# funk.net
KiCad netlist of a schematic drawn in EAGLE
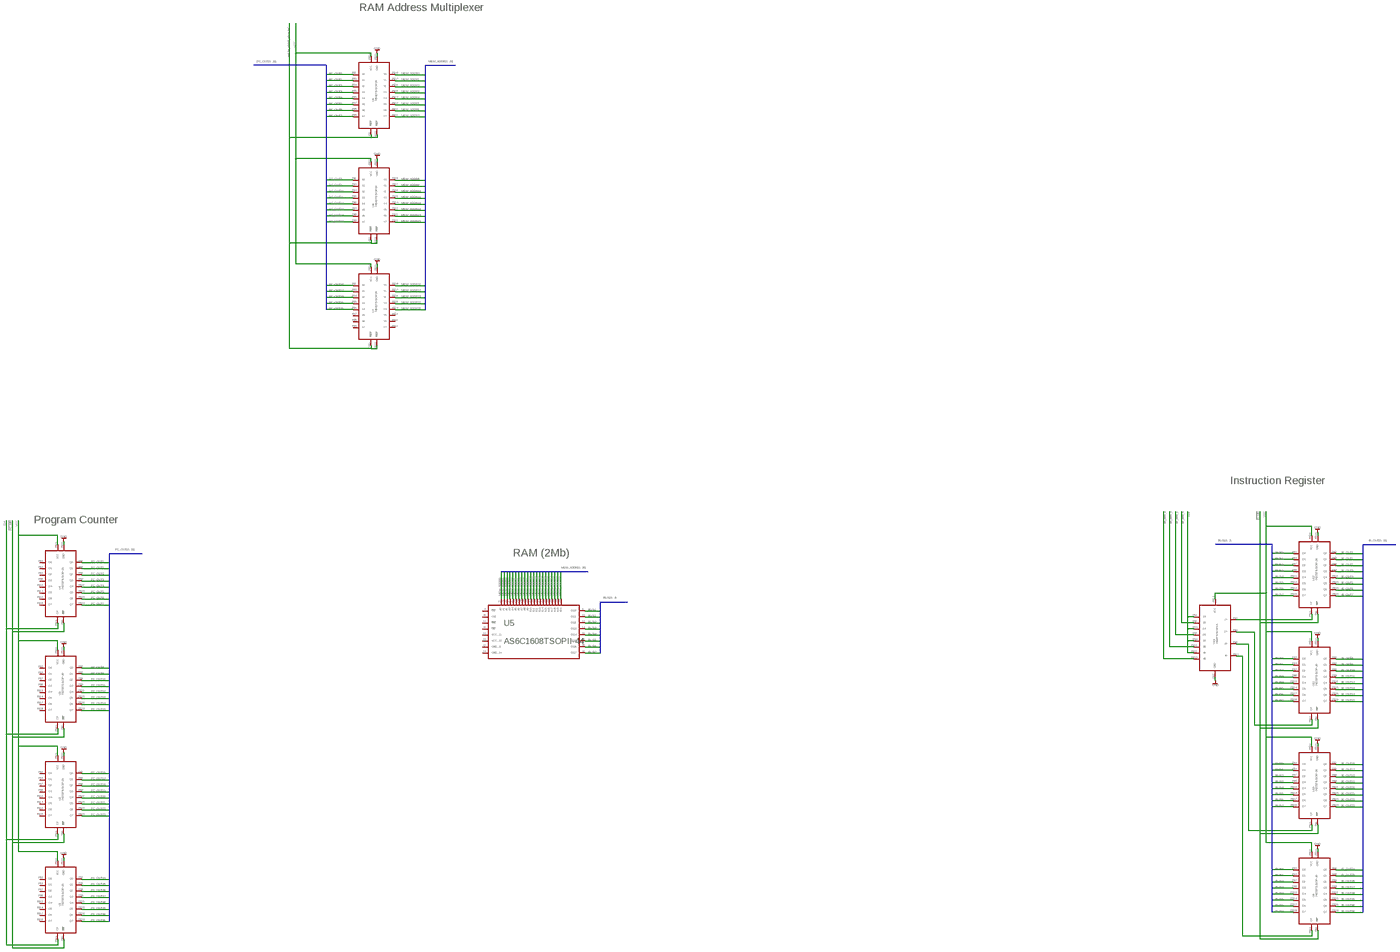
[diagram p0: schematic, sheet 1, overview]
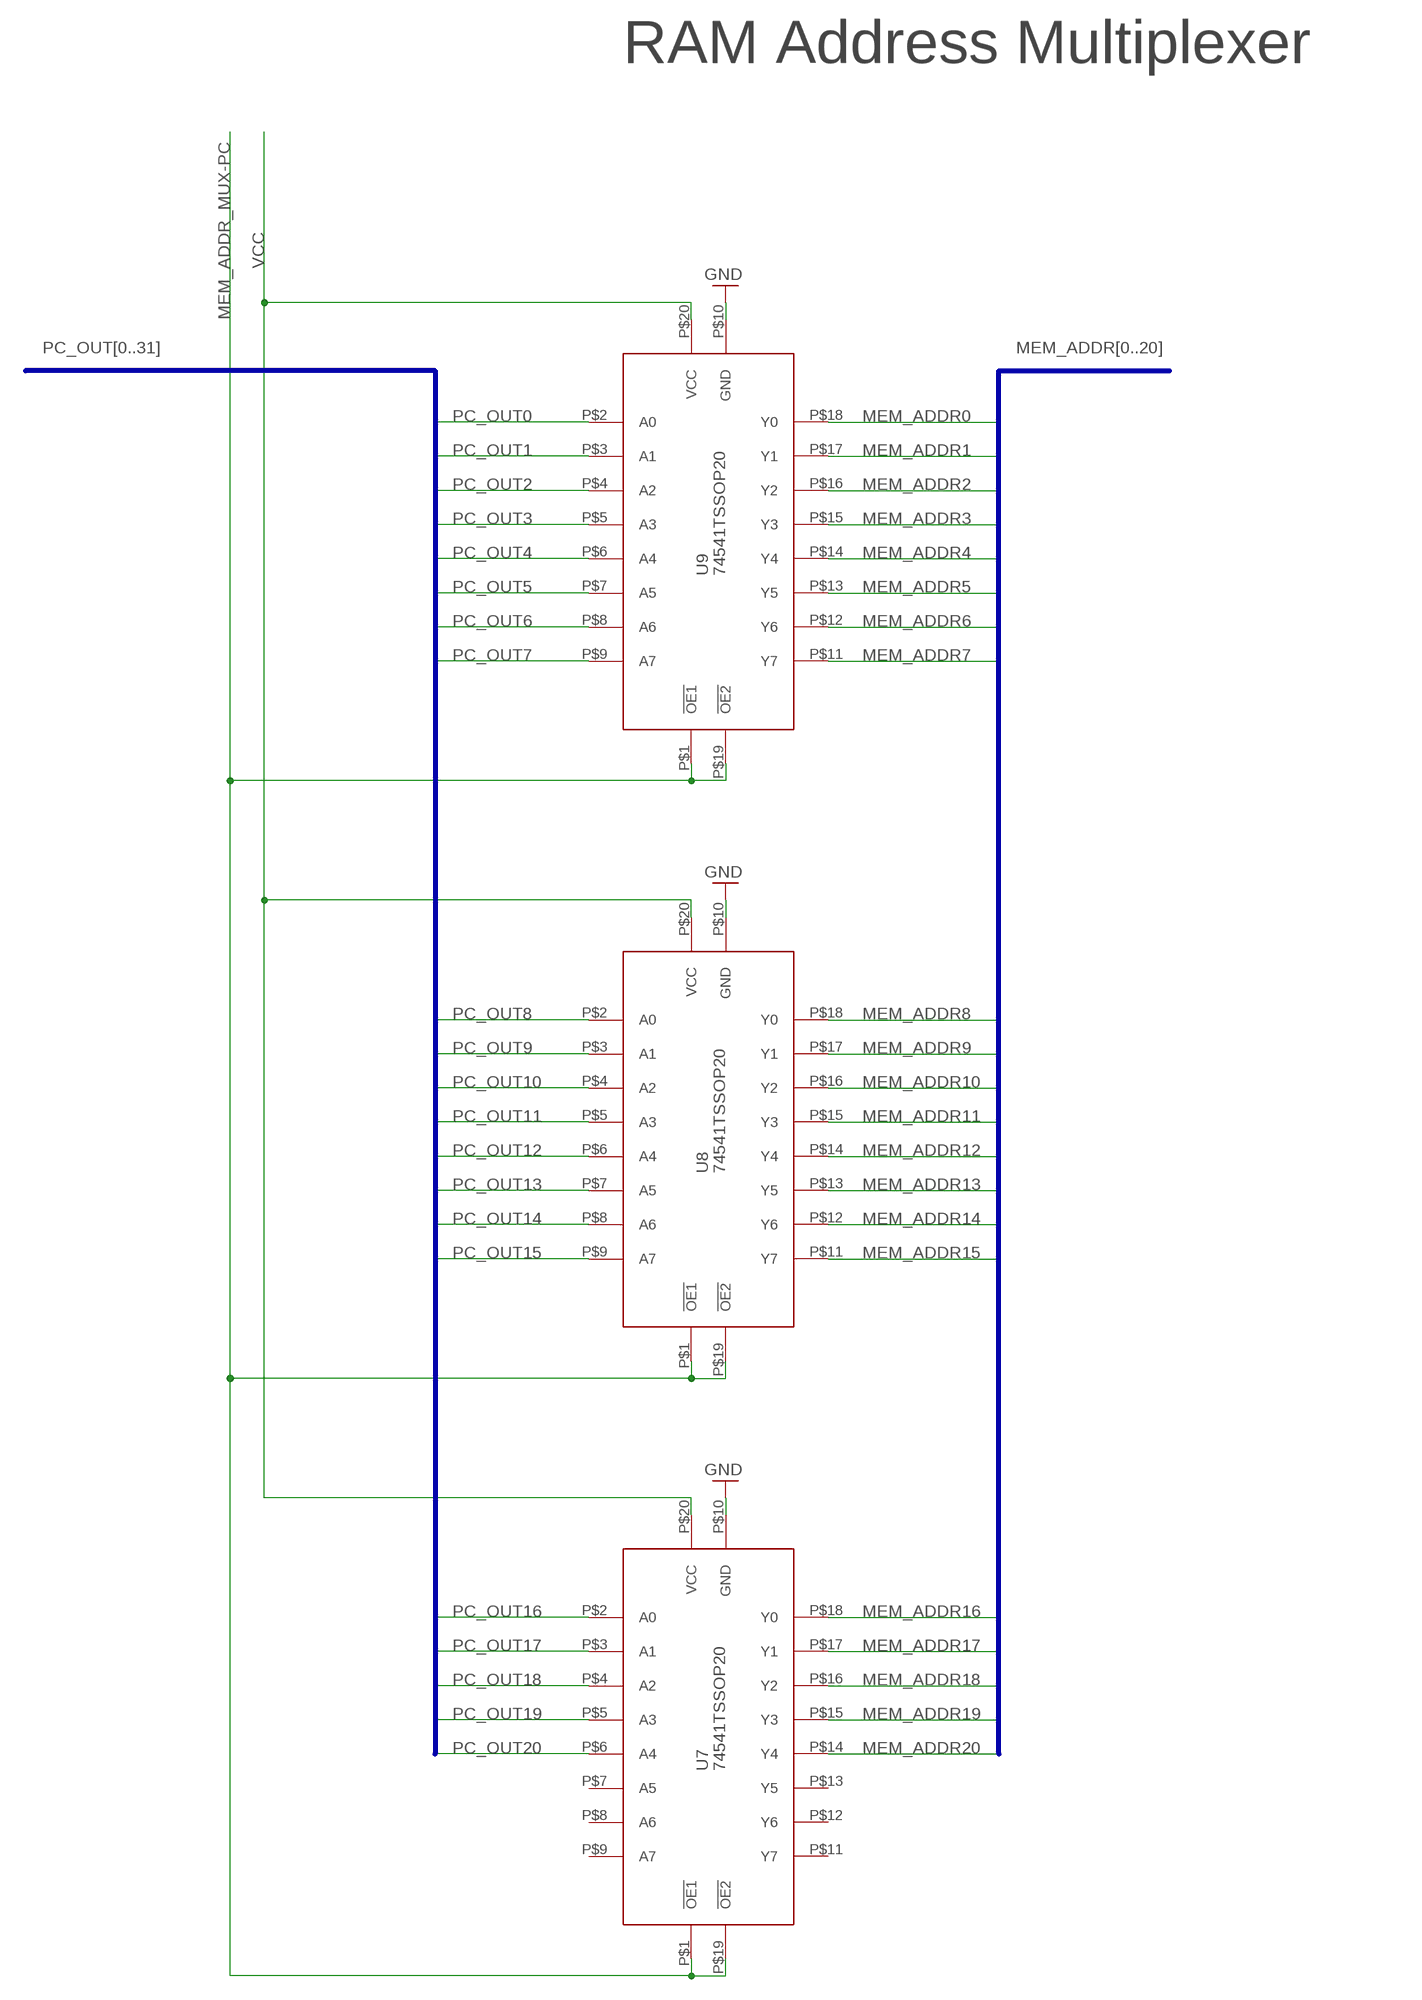
[diagram p1: schematic, sheet 1, part 1 of 4]
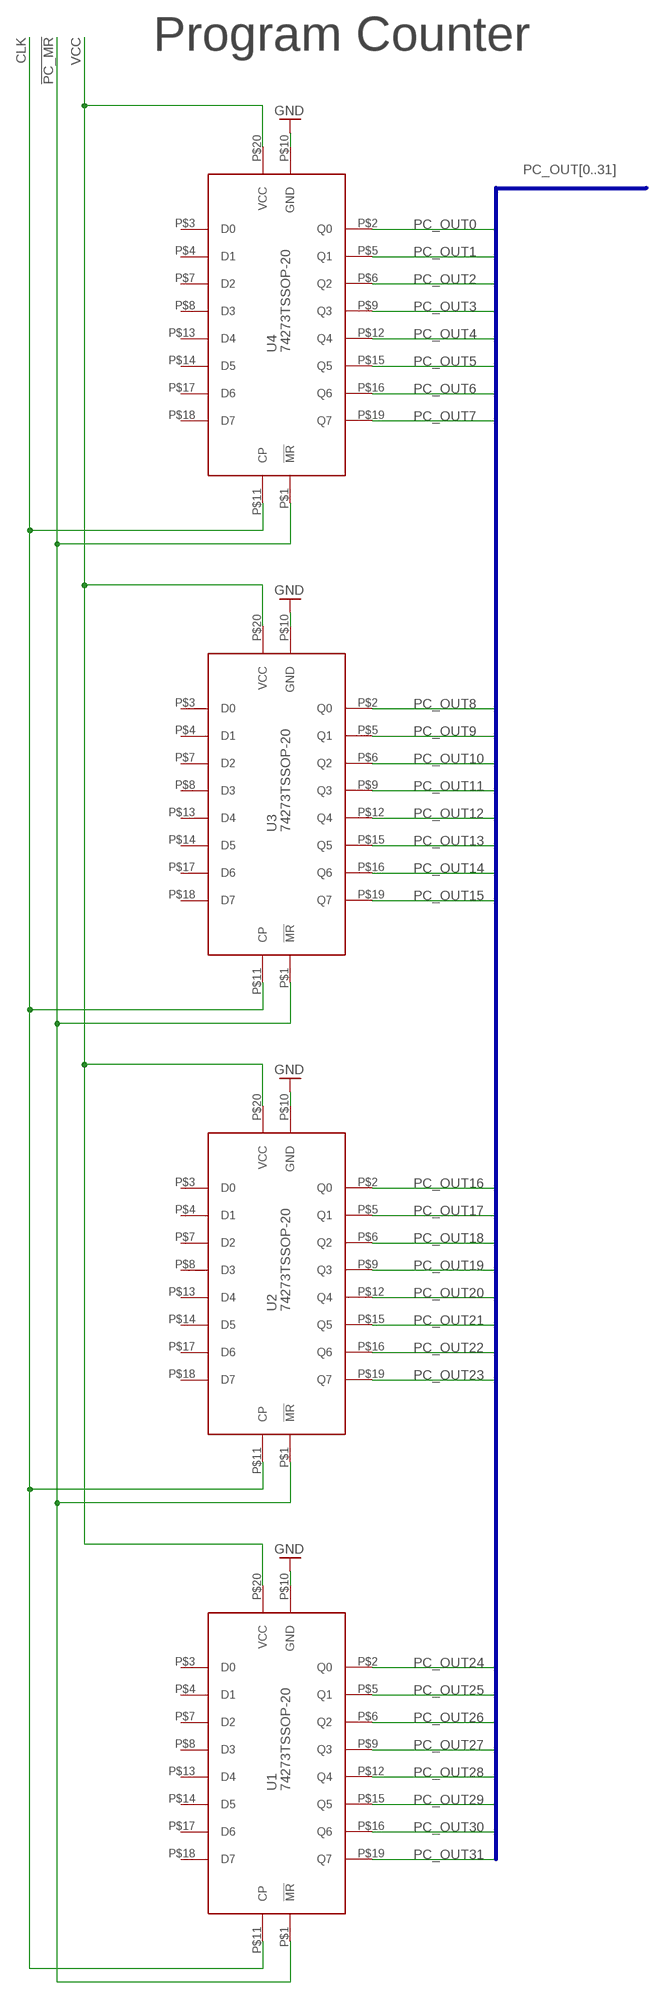
[diagram p2: schematic, sheet 1, part 2 of 4]
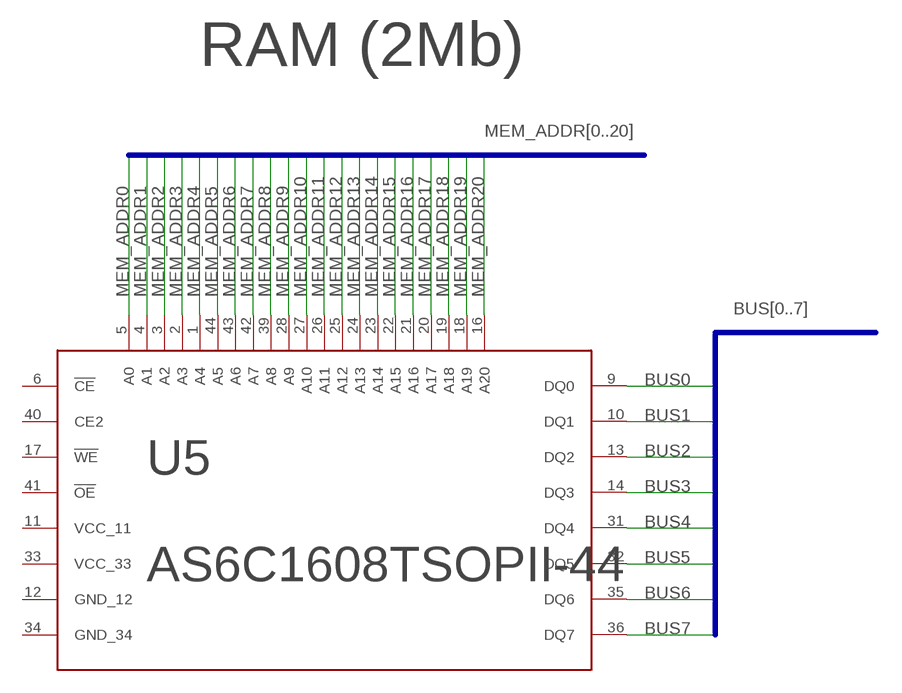
[diagram p3: schematic, sheet 1, part 3 of 4]
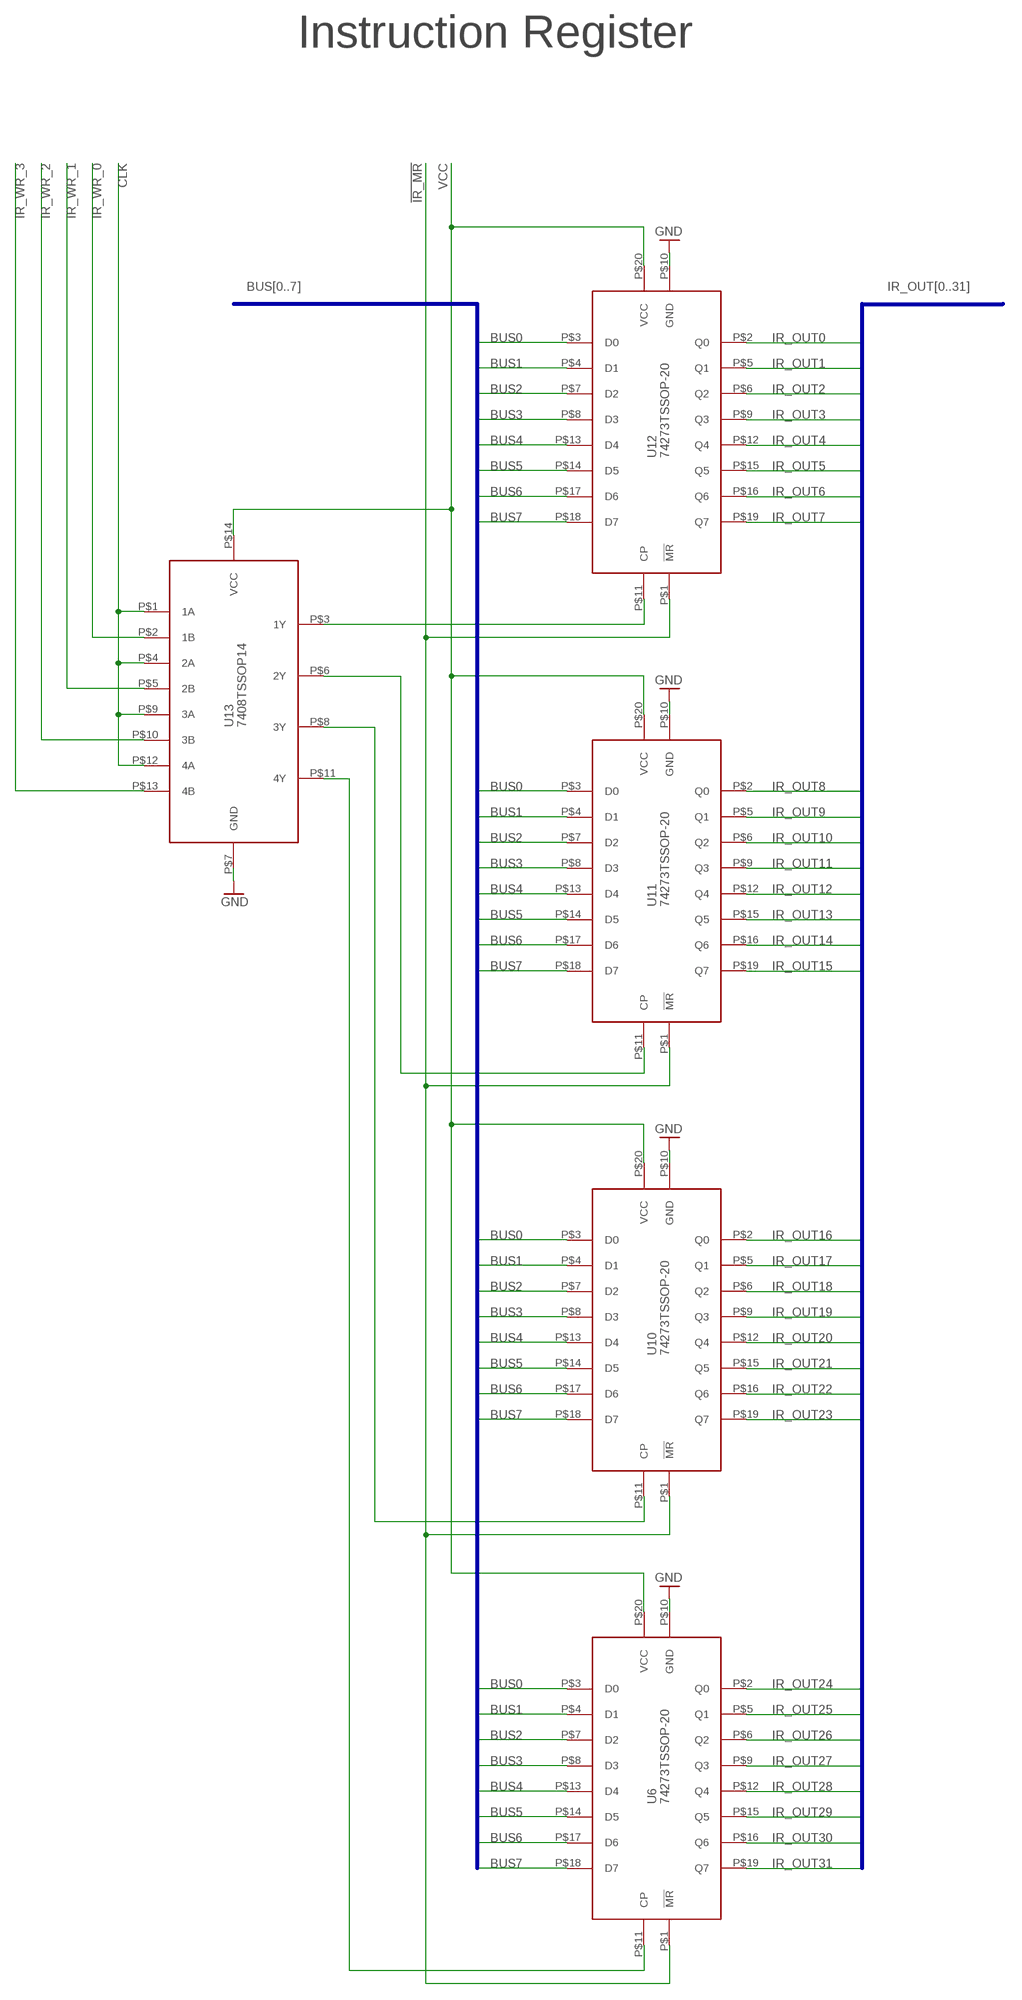
[diagram p4: schematic, sheet 1, part 4 of 4]

(export (version "E")
  (design (tool "Eeschema 10.0.6"))
  (components
    (comp (ref "U1")
      (value "74273TSSOP-20")
      (footprint "eagle-import:TSSOP-20")
      (libsource (lib "eagle-import") (part "74273TSSOP-20"))
    )
    (comp (ref "U2")
      (value "74273TSSOP-20")
      (footprint "eagle-import:TSSOP-20")
      (libsource (lib "eagle-import") (part "74273TSSOP-20"))
    )
    (comp (ref "U3")
      (value "74273TSSOP-20")
      (footprint "eagle-import:TSSOP-20")
      (libsource (lib "eagle-import") (part "74273TSSOP-20"))
    )
    (comp (ref "U4")
      (value "74273TSSOP-20")
      (footprint "eagle-import:TSSOP-20")
      (libsource (lib "eagle-import") (part "74273TSSOP-20"))
    )
    (comp (ref "U5")
      (value "AS6C1608TSOPII-44")
      (footprint "eagle-import:TSOPII-44")
      (libsource (lib "eagle-import") (part "AS6C1608TSOPII-44"))
    )
    (comp (ref "U6")
      (value "74273TSSOP-20")
      (footprint "eagle-import:TSSOP-20")
      (libsource (lib "eagle-import") (part "74273TSSOP-20"))
    )
    (comp (ref "U7")
      (value "74541TSSOP20")
      (footprint "eagle-import:TSSOP-20")
      (libsource (lib "eagle-import") (part "74541TSSOP20"))
    )
    (comp (ref "U8")
      (value "74541TSSOP20")
      (footprint "eagle-import:TSSOP-20")
      (libsource (lib "eagle-import") (part "74541TSSOP20"))
    )
    (comp (ref "U9")
      (value "74541TSSOP20")
      (footprint "eagle-import:TSSOP-20")
      (libsource (lib "eagle-import") (part "74541TSSOP20"))
    )
    (comp (ref "U10")
      (value "74273TSSOP-20")
      (footprint "eagle-import:TSSOP-20")
      (libsource (lib "eagle-import") (part "74273TSSOP-20"))
    )
    (comp (ref "U11")
      (value "74273TSSOP-20")
      (footprint "eagle-import:TSSOP-20")
      (libsource (lib "eagle-import") (part "74273TSSOP-20"))
    )
    (comp (ref "U12")
      (value "74273TSSOP-20")
      (footprint "eagle-import:TSSOP-20")
      (libsource (lib "eagle-import") (part "74273TSSOP-20"))
    )
    (comp (ref "U13")
      (value "7408TSSOP14")
      (footprint "eagle-import:TSSOP-14")
      (libsource (lib "eagle-import") (part "7408TSSOP14"))
    )
  )
  (nets
    (net (code "1") (name "/BUS0") (class "Default")
      (node (ref "U10") (pin "P$3") (pinfunction "D0_P$3") (pintype "bidirectional"))
      (node (ref "U11") (pin "P$3") (pinfunction "D0_P$3") (pintype "bidirectional"))
      (node (ref "U12") (pin "P$3") (pinfunction "D0_P$3") (pintype "bidirectional"))
      (node (ref "U5") (pin "9") (pinfunction "DQ0_9") (pintype "bidirectional"))
      (node (ref "U6") (pin "P$3") (pinfunction "D0_P$3") (pintype "bidirectional"))
    )
    (net (code "2") (name "/BUS1") (class "Default")
      (node (ref "U10") (pin "P$4") (pinfunction "D1_P$4") (pintype "bidirectional"))
      (node (ref "U11") (pin "P$4") (pinfunction "D1_P$4") (pintype "bidirectional"))
      (node (ref "U12") (pin "P$4") (pinfunction "D1_P$4") (pintype "bidirectional"))
      (node (ref "U5") (pin "10") (pinfunction "DQ1_10") (pintype "bidirectional"))
      (node (ref "U6") (pin "P$4") (pinfunction "D1_P$4") (pintype "bidirectional"))
    )
    (net (code "3") (name "/BUS2") (class "Default")
      (node (ref "U10") (pin "P$7") (pinfunction "D2_P$7") (pintype "bidirectional"))
      (node (ref "U11") (pin "P$7") (pinfunction "D2_P$7") (pintype "bidirectional"))
      (node (ref "U12") (pin "P$7") (pinfunction "D2_P$7") (pintype "bidirectional"))
      (node (ref "U5") (pin "13") (pinfunction "DQ2_13") (pintype "bidirectional"))
      (node (ref "U6") (pin "P$7") (pinfunction "D2_P$7") (pintype "bidirectional"))
    )
    (net (code "4") (name "/BUS3") (class "Default")
      (node (ref "U10") (pin "P$8") (pinfunction "D3_P$8") (pintype "bidirectional"))
      (node (ref "U11") (pin "P$8") (pinfunction "D3_P$8") (pintype "bidirectional"))
      (node (ref "U12") (pin "P$8") (pinfunction "D3_P$8") (pintype "bidirectional"))
      (node (ref "U5") (pin "14") (pinfunction "DQ3_14") (pintype "bidirectional"))
      (node (ref "U6") (pin "P$8") (pinfunction "D3_P$8") (pintype "bidirectional"))
    )
    (net (code "5") (name "/BUS4") (class "Default")
      (node (ref "U10") (pin "P$13") (pinfunction "D4_P$13") (pintype "bidirectional"))
      (node (ref "U11") (pin "P$13") (pinfunction "D4_P$13") (pintype "bidirectional"))
      (node (ref "U12") (pin "P$13") (pinfunction "D4_P$13") (pintype "bidirectional"))
      (node (ref "U5") (pin "31") (pinfunction "DQ4_31") (pintype "bidirectional"))
      (node (ref "U6") (pin "P$13") (pinfunction "D4_P$13") (pintype "bidirectional"))
    )
    (net (code "6") (name "/BUS5") (class "Default")
      (node (ref "U10") (pin "P$14") (pinfunction "D5_P$14") (pintype "bidirectional"))
      (node (ref "U11") (pin "P$14") (pinfunction "D5_P$14") (pintype "bidirectional"))
      (node (ref "U12") (pin "P$14") (pinfunction "D5_P$14") (pintype "bidirectional"))
      (node (ref "U5") (pin "32") (pinfunction "DQ5_32") (pintype "bidirectional"))
      (node (ref "U6") (pin "P$14") (pinfunction "D5_P$14") (pintype "bidirectional"))
    )
    (net (code "7") (name "/BUS6") (class "Default")
      (node (ref "U10") (pin "P$17") (pinfunction "D6_P$17") (pintype "bidirectional"))
      (node (ref "U11") (pin "P$17") (pinfunction "D6_P$17") (pintype "bidirectional"))
      (node (ref "U12") (pin "P$17") (pinfunction "D6_P$17") (pintype "bidirectional"))
      (node (ref "U5") (pin "35") (pinfunction "DQ6_35") (pintype "bidirectional"))
      (node (ref "U6") (pin "P$17") (pinfunction "D6_P$17") (pintype "bidirectional"))
    )
    (net (code "8") (name "/BUS7") (class "Default")
      (node (ref "U10") (pin "P$18") (pinfunction "D7_P$18") (pintype "bidirectional"))
      (node (ref "U11") (pin "P$18") (pinfunction "D7_P$18") (pintype "bidirectional"))
      (node (ref "U12") (pin "P$18") (pinfunction "D7_P$18") (pintype "bidirectional"))
      (node (ref "U5") (pin "36") (pinfunction "DQ7_36") (pintype "bidirectional"))
      (node (ref "U6") (pin "P$18") (pinfunction "D7_P$18") (pintype "bidirectional"))
    )
    (net (code "10") (name "/CLK") (class "Default")
      (node (ref "U1") (pin "P$11") (pinfunction "CP_P$11") (pintype "bidirectional"))
      (node (ref "U10") (pin "P$11") (pinfunction "CP_P$11") (pintype "bidirectional"))
      (node (ref "U13") (pin "P$1") (pinfunction "1A_P$1") (pintype "bidirectional"))
      (node (ref "U13") (pin "P$12") (pinfunction "4A_P$12") (pintype "bidirectional"))
      (node (ref "U13") (pin "P$4") (pinfunction "2A_P$4") (pintype "bidirectional"))
      (node (ref "U13") (pin "P$8") (pinfunction "3Y_P$8") (pintype "bidirectional"))
      (node (ref "U13") (pin "P$9") (pinfunction "3A_P$9") (pintype "bidirectional"))
      (node (ref "U2") (pin "P$11") (pinfunction "CP_P$11") (pintype "bidirectional"))
      (node (ref "U3") (pin "P$11") (pinfunction "CP_P$11") (pintype "bidirectional"))
      (node (ref "U4") (pin "P$11") (pinfunction "CP_P$11") (pintype "bidirectional"))
    )
    (net (code "11") (name "/IR_OUT0") (class "Default")
      (node (ref "U12") (pin "P$2") (pinfunction "Q0_P$2") (pintype "bidirectional"))
    )
    (net (code "12") (name "/IR_OUT1") (class "Default")
      (node (ref "U12") (pin "P$5") (pinfunction "Q1_P$5") (pintype "bidirectional"))
    )
    (net (code "13") (name "/IR_OUT2") (class "Default")
      (node (ref "U12") (pin "P$6") (pinfunction "Q2_P$6") (pintype "bidirectional"))
    )
    (net (code "14") (name "/IR_OUT3") (class "Default")
      (node (ref "U12") (pin "P$9") (pinfunction "Q3_P$9") (pintype "bidirectional"))
    )
    (net (code "15") (name "/IR_OUT4") (class "Default")
      (node (ref "U12") (pin "P$12") (pinfunction "Q4_P$12") (pintype "bidirectional"))
    )
    (net (code "16") (name "/IR_OUT5") (class "Default")
      (node (ref "U12") (pin "P$15") (pinfunction "Q5_P$15") (pintype "bidirectional"))
    )
    (net (code "17") (name "/IR_OUT6") (class "Default")
      (node (ref "U12") (pin "P$16") (pinfunction "Q6_P$16") (pintype "bidirectional"))
    )
    (net (code "18") (name "/IR_OUT7") (class "Default")
      (node (ref "U12") (pin "P$19") (pinfunction "Q7_P$19") (pintype "bidirectional"))
    )
    (net (code "19") (name "/IR_OUT8") (class "Default")
      (node (ref "U11") (pin "P$2") (pinfunction "Q0_P$2") (pintype "bidirectional"))
    )
    (net (code "20") (name "/IR_OUT9") (class "Default")
      (node (ref "U11") (pin "P$5") (pinfunction "Q1_P$5") (pintype "bidirectional"))
    )
    (net (code "21") (name "/IR_OUT10") (class "Default")
      (node (ref "U11") (pin "P$6") (pinfunction "Q2_P$6") (pintype "bidirectional"))
    )
    (net (code "22") (name "/IR_OUT11") (class "Default")
      (node (ref "U11") (pin "P$9") (pinfunction "Q3_P$9") (pintype "bidirectional"))
    )
    (net (code "23") (name "/IR_OUT12") (class "Default")
      (node (ref "U11") (pin "P$12") (pinfunction "Q4_P$12") (pintype "bidirectional"))
    )
    (net (code "24") (name "/IR_OUT13") (class "Default")
      (node (ref "U11") (pin "P$15") (pinfunction "Q5_P$15") (pintype "bidirectional"))
    )
    (net (code "25") (name "/IR_OUT14") (class "Default")
      (node (ref "U11") (pin "P$16") (pinfunction "Q6_P$16") (pintype "bidirectional"))
    )
    (net (code "26") (name "/IR_OUT15") (class "Default")
      (node (ref "U11") (pin "P$19") (pinfunction "Q7_P$19") (pintype "bidirectional"))
    )
    (net (code "27") (name "/IR_OUT16") (class "Default")
      (node (ref "U10") (pin "P$2") (pinfunction "Q0_P$2") (pintype "bidirectional"))
    )
    (net (code "28") (name "/IR_OUT17") (class "Default")
      (node (ref "U10") (pin "P$5") (pinfunction "Q1_P$5") (pintype "bidirectional"))
    )
    (net (code "29") (name "/IR_OUT18") (class "Default")
      (node (ref "U10") (pin "P$6") (pinfunction "Q2_P$6") (pintype "bidirectional"))
    )
    (net (code "30") (name "/IR_OUT19") (class "Default")
      (node (ref "U10") (pin "P$9") (pinfunction "Q3_P$9") (pintype "bidirectional"))
    )
    (net (code "31") (name "/IR_OUT20") (class "Default")
      (node (ref "U10") (pin "P$12") (pinfunction "Q4_P$12") (pintype "bidirectional"))
    )
    (net (code "32") (name "/IR_OUT21") (class "Default")
      (node (ref "U10") (pin "P$15") (pinfunction "Q5_P$15") (pintype "bidirectional"))
    )
    (net (code "33") (name "/IR_OUT22") (class "Default")
      (node (ref "U10") (pin "P$16") (pinfunction "Q6_P$16") (pintype "bidirectional"))
    )
    (net (code "34") (name "/IR_OUT23") (class "Default")
      (node (ref "U10") (pin "P$19") (pinfunction "Q7_P$19") (pintype "bidirectional"))
    )
    (net (code "35") (name "/IR_OUT24") (class "Default")
      (node (ref "U6") (pin "P$2") (pinfunction "Q0_P$2") (pintype "bidirectional"))
    )
    (net (code "36") (name "/IR_OUT25") (class "Default")
      (node (ref "U6") (pin "P$5") (pinfunction "Q1_P$5") (pintype "bidirectional"))
    )
    (net (code "37") (name "/IR_OUT26") (class "Default")
      (node (ref "U6") (pin "P$6") (pinfunction "Q2_P$6") (pintype "bidirectional"))
    )
    (net (code "38") (name "/IR_OUT27") (class "Default")
      (node (ref "U6") (pin "P$9") (pinfunction "Q3_P$9") (pintype "bidirectional"))
    )
    (net (code "39") (name "/IR_OUT28") (class "Default")
      (node (ref "U6") (pin "P$12") (pinfunction "Q4_P$12") (pintype "bidirectional"))
    )
    (net (code "40") (name "/IR_OUT29") (class "Default")
      (node (ref "U6") (pin "P$15") (pinfunction "Q5_P$15") (pintype "bidirectional"))
    )
    (net (code "41") (name "/IR_OUT30") (class "Default")
      (node (ref "U6") (pin "P$16") (pinfunction "Q6_P$16") (pintype "bidirectional"))
    )
    (net (code "42") (name "/IR_OUT31") (class "Default")
      (node (ref "U6") (pin "P$19") (pinfunction "Q7_P$19") (pintype "bidirectional"))
    )
    (net (code "44") (name "/IR_WR_0") (class "Default")
      (node (ref "U13") (pin "P$2") (pinfunction "1B_P$2") (pintype "bidirectional"))
    )
    (net (code "45") (name "/IR_WR_1") (class "Default")
      (node (ref "U13") (pin "P$5") (pinfunction "2B_P$5") (pintype "bidirectional"))
    )
    (net (code "46") (name "/IR_WR_2") (class "Default")
      (node (ref "U13") (pin "P$10") (pinfunction "3B_P$10") (pintype "bidirectional"))
    )
    (net (code "47") (name "/IR_WR_3") (class "Default")
      (node (ref "U13") (pin "P$13") (pinfunction "4B_P$13") (pintype "bidirectional"))
    )
    (net (code "48") (name "/MEM_ADDR0") (class "Default")
      (node (ref "U5") (pin "5") (pinfunction "A0_5") (pintype "bidirectional"))
      (node (ref "U9") (pin "P$18") (pinfunction "Y0_P$18") (pintype "bidirectional"))
    )
    (net (code "49") (name "/MEM_ADDR1") (class "Default")
      (node (ref "U5") (pin "4") (pinfunction "A1_4") (pintype "bidirectional"))
      (node (ref "U9") (pin "P$17") (pinfunction "Y1_P$17") (pintype "bidirectional"))
    )
    (net (code "50") (name "/MEM_ADDR2") (class "Default")
      (node (ref "U5") (pin "3") (pinfunction "A2_3") (pintype "bidirectional"))
      (node (ref "U9") (pin "P$16") (pinfunction "Y2_P$16") (pintype "bidirectional"))
    )
    (net (code "51") (name "/MEM_ADDR3") (class "Default")
      (node (ref "U5") (pin "2") (pinfunction "A3_2") (pintype "bidirectional"))
      (node (ref "U9") (pin "P$15") (pinfunction "Y3_P$15") (pintype "bidirectional"))
    )
    (net (code "52") (name "/MEM_ADDR4") (class "Default")
      (node (ref "U5") (pin "1") (pinfunction "A4_1") (pintype "bidirectional"))
      (node (ref "U9") (pin "P$14") (pinfunction "Y4_P$14") (pintype "bidirectional"))
    )
    (net (code "53") (name "/MEM_ADDR5") (class "Default")
      (node (ref "U5") (pin "44") (pinfunction "A5_44") (pintype "bidirectional"))
      (node (ref "U9") (pin "P$13") (pinfunction "Y5_P$13") (pintype "bidirectional"))
    )
    (net (code "54") (name "/MEM_ADDR6") (class "Default")
      (node (ref "U5") (pin "43") (pinfunction "A6_43") (pintype "bidirectional"))
      (node (ref "U9") (pin "P$12") (pinfunction "Y6_P$12") (pintype "bidirectional"))
    )
    (net (code "55") (name "/MEM_ADDR7") (class "Default")
      (node (ref "U5") (pin "42") (pinfunction "A7_42") (pintype "bidirectional"))
      (node (ref "U9") (pin "P$11") (pinfunction "Y7_P$11") (pintype "bidirectional"))
    )
    (net (code "56") (name "/MEM_ADDR8") (class "Default")
      (node (ref "U5") (pin "39") (pinfunction "A8_39") (pintype "bidirectional"))
      (node (ref "U8") (pin "P$18") (pinfunction "Y0_P$18") (pintype "bidirectional"))
    )
    (net (code "57") (name "/MEM_ADDR9") (class "Default")
      (node (ref "U5") (pin "28") (pinfunction "A9_28") (pintype "bidirectional"))
      (node (ref "U8") (pin "P$17") (pinfunction "Y1_P$17") (pintype "bidirectional"))
    )
    (net (code "58") (name "/MEM_ADDR10") (class "Default")
      (node (ref "U5") (pin "27") (pinfunction "A10_27") (pintype "bidirectional"))
      (node (ref "U8") (pin "P$16") (pinfunction "Y2_P$16") (pintype "bidirectional"))
    )
    (net (code "59") (name "/MEM_ADDR11") (class "Default")
      (node (ref "U5") (pin "26") (pinfunction "A11_26") (pintype "bidirectional"))
      (node (ref "U8") (pin "P$15") (pinfunction "Y3_P$15") (pintype "bidirectional"))
    )
    (net (code "60") (name "/MEM_ADDR12") (class "Default")
      (node (ref "U5") (pin "25") (pinfunction "A12_25") (pintype "bidirectional"))
      (node (ref "U8") (pin "P$14") (pinfunction "Y4_P$14") (pintype "bidirectional"))
    )
    (net (code "61") (name "/MEM_ADDR13") (class "Default")
      (node (ref "U5") (pin "24") (pinfunction "A13_24") (pintype "bidirectional"))
      (node (ref "U8") (pin "P$13") (pinfunction "Y5_P$13") (pintype "bidirectional"))
    )
    (net (code "62") (name "/MEM_ADDR14") (class "Default")
      (node (ref "U5") (pin "23") (pinfunction "A14_23") (pintype "bidirectional"))
      (node (ref "U8") (pin "P$12") (pinfunction "Y6_P$12") (pintype "bidirectional"))
    )
    (net (code "63") (name "/MEM_ADDR15") (class "Default")
      (node (ref "U5") (pin "22") (pinfunction "A15_22") (pintype "bidirectional"))
      (node (ref "U8") (pin "P$11") (pinfunction "Y7_P$11") (pintype "bidirectional"))
    )
    (net (code "64") (name "/MEM_ADDR16") (class "Default")
      (node (ref "U5") (pin "21") (pinfunction "A16_21") (pintype "bidirectional"))
      (node (ref "U7") (pin "P$18") (pinfunction "Y0_P$18") (pintype "bidirectional"))
    )
    (net (code "65") (name "/MEM_ADDR17") (class "Default")
      (node (ref "U5") (pin "20") (pinfunction "A17_20") (pintype "bidirectional"))
      (node (ref "U7") (pin "P$17") (pinfunction "Y1_P$17") (pintype "bidirectional"))
    )
    (net (code "66") (name "/MEM_ADDR18") (class "Default")
      (node (ref "U5") (pin "19") (pinfunction "A18_19") (pintype "bidirectional"))
      (node (ref "U7") (pin "P$16") (pinfunction "Y2_P$16") (pintype "bidirectional"))
    )
    (net (code "67") (name "/MEM_ADDR19") (class "Default")
      (node (ref "U5") (pin "18") (pinfunction "A19_18") (pintype "bidirectional"))
      (node (ref "U7") (pin "P$15") (pinfunction "Y3_P$15") (pintype "bidirectional"))
    )
    (net (code "68") (name "/MEM_ADDR20") (class "Default")
      (node (ref "U5") (pin "16") (pinfunction "A20_16") (pintype "bidirectional"))
      (node (ref "U7") (pin "P$14") (pinfunction "Y4_P$14") (pintype "bidirectional"))
    )
    (net (code "70") (name "/MEM_ADDR_MUX-PC") (class "Default")
      (node (ref "U7") (pin "P$1") (pinfunction "~{OE1}_P$1") (pintype "bidirectional"))
      (node (ref "U7") (pin "P$19") (pinfunction "~{OE2}_P$19") (pintype "bidirectional"))
      (node (ref "U8") (pin "P$1") (pinfunction "~{OE1}_P$1") (pintype "bidirectional"))
      (node (ref "U8") (pin "P$19") (pinfunction "~{OE2}_P$19") (pintype "bidirectional"))
      (node (ref "U9") (pin "P$1") (pinfunction "~{OE1}_P$1") (pintype "bidirectional"))
      (node (ref "U9") (pin "P$19") (pinfunction "~{OE2}_P$19") (pintype "bidirectional"))
    )
    (net (code "71") (name "/PC_OUT0") (class "Default")
      (node (ref "U4") (pin "P$2") (pinfunction "Q0_P$2") (pintype "bidirectional"))
      (node (ref "U9") (pin "P$2") (pinfunction "A0_P$2") (pintype "bidirectional"))
    )
    (net (code "72") (name "/PC_OUT1") (class "Default")
      (node (ref "U4") (pin "P$5") (pinfunction "Q1_P$5") (pintype "bidirectional"))
      (node (ref "U9") (pin "P$3") (pinfunction "A1_P$3") (pintype "bidirectional"))
    )
    (net (code "73") (name "/PC_OUT2") (class "Default")
      (node (ref "U4") (pin "P$6") (pinfunction "Q2_P$6") (pintype "bidirectional"))
      (node (ref "U9") (pin "P$4") (pinfunction "A2_P$4") (pintype "bidirectional"))
    )
    (net (code "74") (name "/PC_OUT3") (class "Default")
      (node (ref "U4") (pin "P$9") (pinfunction "Q3_P$9") (pintype "bidirectional"))
      (node (ref "U9") (pin "P$5") (pinfunction "A3_P$5") (pintype "bidirectional"))
    )
    (net (code "75") (name "/PC_OUT4") (class "Default")
      (node (ref "U4") (pin "P$12") (pinfunction "Q4_P$12") (pintype "bidirectional"))
      (node (ref "U9") (pin "P$6") (pinfunction "A4_P$6") (pintype "bidirectional"))
    )
    (net (code "76") (name "/PC_OUT5") (class "Default")
      (node (ref "U4") (pin "P$15") (pinfunction "Q5_P$15") (pintype "bidirectional"))
      (node (ref "U9") (pin "P$7") (pinfunction "A5_P$7") (pintype "bidirectional"))
    )
    (net (code "77") (name "/PC_OUT6") (class "Default")
      (node (ref "U4") (pin "P$16") (pinfunction "Q6_P$16") (pintype "bidirectional"))
      (node (ref "U9") (pin "P$8") (pinfunction "A6_P$8") (pintype "bidirectional"))
    )
    (net (code "78") (name "/PC_OUT7") (class "Default")
      (node (ref "U4") (pin "P$19") (pinfunction "Q7_P$19") (pintype "bidirectional"))
      (node (ref "U9") (pin "P$9") (pinfunction "A7_P$9") (pintype "bidirectional"))
    )
    (net (code "79") (name "/PC_OUT8") (class "Default")
      (node (ref "U3") (pin "P$2") (pinfunction "Q0_P$2") (pintype "bidirectional"))
      (node (ref "U8") (pin "P$2") (pinfunction "A0_P$2") (pintype "bidirectional"))
    )
    (net (code "80") (name "/PC_OUT9") (class "Default")
      (node (ref "U3") (pin "P$5") (pinfunction "Q1_P$5") (pintype "bidirectional"))
      (node (ref "U8") (pin "P$3") (pinfunction "A1_P$3") (pintype "bidirectional"))
    )
    (net (code "81") (name "/PC_OUT10") (class "Default")
      (node (ref "U3") (pin "P$6") (pinfunction "Q2_P$6") (pintype "bidirectional"))
      (node (ref "U8") (pin "P$4") (pinfunction "A2_P$4") (pintype "bidirectional"))
    )
    (net (code "82") (name "/PC_OUT11") (class "Default")
      (node (ref "U3") (pin "P$9") (pinfunction "Q3_P$9") (pintype "bidirectional"))
      (node (ref "U8") (pin "P$5") (pinfunction "A3_P$5") (pintype "bidirectional"))
    )
    (net (code "83") (name "/PC_OUT12") (class "Default")
      (node (ref "U3") (pin "P$12") (pinfunction "Q4_P$12") (pintype "bidirectional"))
      (node (ref "U8") (pin "P$6") (pinfunction "A4_P$6") (pintype "bidirectional"))
    )
    (net (code "84") (name "/PC_OUT13") (class "Default")
      (node (ref "U3") (pin "P$15") (pinfunction "Q5_P$15") (pintype "bidirectional"))
      (node (ref "U8") (pin "P$7") (pinfunction "A5_P$7") (pintype "bidirectional"))
    )
    (net (code "85") (name "/PC_OUT14") (class "Default")
      (node (ref "U3") (pin "P$16") (pinfunction "Q6_P$16") (pintype "bidirectional"))
      (node (ref "U8") (pin "P$8") (pinfunction "A6_P$8") (pintype "bidirectional"))
    )
    (net (code "86") (name "/PC_OUT15") (class "Default")
      (node (ref "U3") (pin "P$19") (pinfunction "Q7_P$19") (pintype "bidirectional"))
      (node (ref "U8") (pin "P$9") (pinfunction "A7_P$9") (pintype "bidirectional"))
    )
    (net (code "87") (name "/PC_OUT16") (class "Default")
      (node (ref "U2") (pin "P$2") (pinfunction "Q0_P$2") (pintype "bidirectional"))
      (node (ref "U7") (pin "P$2") (pinfunction "A0_P$2") (pintype "bidirectional"))
    )
    (net (code "88") (name "/PC_OUT17") (class "Default")
      (node (ref "U2") (pin "P$5") (pinfunction "Q1_P$5") (pintype "bidirectional"))
      (node (ref "U7") (pin "P$3") (pinfunction "A1_P$3") (pintype "bidirectional"))
    )
    (net (code "89") (name "/PC_OUT18") (class "Default")
      (node (ref "U2") (pin "P$6") (pinfunction "Q2_P$6") (pintype "bidirectional"))
      (node (ref "U7") (pin "P$4") (pinfunction "A2_P$4") (pintype "bidirectional"))
    )
    (net (code "90") (name "/PC_OUT19") (class "Default")
      (node (ref "U2") (pin "P$9") (pinfunction "Q3_P$9") (pintype "bidirectional"))
      (node (ref "U7") (pin "P$5") (pinfunction "A3_P$5") (pintype "bidirectional"))
    )
    (net (code "91") (name "/PC_OUT20") (class "Default")
      (node (ref "U2") (pin "P$12") (pinfunction "Q4_P$12") (pintype "bidirectional"))
      (node (ref "U7") (pin "P$6") (pinfunction "A4_P$6") (pintype "bidirectional"))
    )
    (net (code "92") (name "/PC_OUT21") (class "Default")
      (node (ref "U2") (pin "P$15") (pinfunction "Q5_P$15") (pintype "bidirectional"))
    )
    (net (code "93") (name "/PC_OUT22") (class "Default")
      (node (ref "U2") (pin "P$16") (pinfunction "Q6_P$16") (pintype "bidirectional"))
    )
    (net (code "94") (name "/PC_OUT23") (class "Default")
      (node (ref "U2") (pin "P$19") (pinfunction "Q7_P$19") (pintype "bidirectional"))
    )
    (net (code "95") (name "/PC_OUT24") (class "Default")
      (node (ref "U1") (pin "P$2") (pinfunction "Q0_P$2") (pintype "bidirectional"))
    )
    (net (code "96") (name "/PC_OUT25") (class "Default")
      (node (ref "U1") (pin "P$5") (pinfunction "Q1_P$5") (pintype "bidirectional"))
    )
    (net (code "97") (name "/PC_OUT26") (class "Default")
      (node (ref "U1") (pin "P$6") (pinfunction "Q2_P$6") (pintype "bidirectional"))
    )
    (net (code "98") (name "/PC_OUT27") (class "Default")
      (node (ref "U1") (pin "P$9") (pinfunction "Q3_P$9") (pintype "bidirectional"))
    )
    (net (code "99") (name "/PC_OUT28") (class "Default")
      (node (ref "U1") (pin "P$12") (pinfunction "Q4_P$12") (pintype "bidirectional"))
    )
    (net (code "100") (name "/PC_OUT29") (class "Default")
      (node (ref "U1") (pin "P$15") (pinfunction "Q5_P$15") (pintype "bidirectional"))
    )
    (net (code "101") (name "/PC_OUT30") (class "Default")
      (node (ref "U1") (pin "P$16") (pinfunction "Q6_P$16") (pintype "bidirectional"))
    )
    (net (code "102") (name "/PC_OUT31") (class "Default")
      (node (ref "U1") (pin "P$19") (pinfunction "Q7_P$19") (pintype "bidirectional"))
    )
    (net (code "104") (name "/VCC") (class "Default")
      (node (ref "U1") (pin "P$20") (pinfunction "VCC_P$20") (pintype "bidirectional"))
      (node (ref "U10") (pin "P$20") (pinfunction "VCC_P$20") (pintype "bidirectional"))
      (node (ref "U11") (pin "P$20") (pinfunction "VCC_P$20") (pintype "bidirectional"))
      (node (ref "U12") (pin "P$20") (pinfunction "VCC_P$20") (pintype "bidirectional"))
      (node (ref "U13") (pin "P$14") (pinfunction "VCC_P$14") (pintype "bidirectional"))
      (node (ref "U2") (pin "P$20") (pinfunction "VCC_P$20") (pintype "bidirectional"))
      (node (ref "U3") (pin "P$20") (pinfunction "VCC_P$20") (pintype "bidirectional"))
      (node (ref "U4") (pin "P$20") (pinfunction "VCC_P$20") (pintype "bidirectional"))
      (node (ref "U6") (pin "P$20") (pinfunction "VCC_P$20") (pintype "bidirectional"))
      (node (ref "U7") (pin "P$20") (pinfunction "VCC_P$20") (pintype "bidirectional"))
      (node (ref "U8") (pin "P$20") (pinfunction "VCC_P$20") (pintype "bidirectional"))
      (node (ref "U9") (pin "P$20") (pinfunction "VCC_P$20") (pintype "bidirectional"))
    )
    (net (code "105") (name "/~{IR_MR}") (class "Default")
      (node (ref "U10") (pin "P$1") (pinfunction "~{MR}_P$1") (pintype "bidirectional"))
      (node (ref "U11") (pin "P$1") (pinfunction "~{MR}_P$1") (pintype "bidirectional"))
      (node (ref "U12") (pin "P$1") (pinfunction "~{MR}_P$1") (pintype "bidirectional"))
      (node (ref "U6") (pin "P$1") (pinfunction "~{MR}_P$1") (pintype "bidirectional"))
    )
    (net (code "106") (name "/~{PC_MR}") (class "Default")
      (node (ref "U1") (pin "P$1") (pinfunction "~{MR}_P$1") (pintype "bidirectional"))
      (node (ref "U2") (pin "P$1") (pinfunction "~{MR}_P$1") (pintype "bidirectional"))
      (node (ref "U3") (pin "P$1") (pinfunction "~{MR}_P$1") (pintype "bidirectional"))
      (node (ref "U4") (pin "P$1") (pinfunction "~{MR}_P$1") (pintype "bidirectional"))
    )
    (net (code "107") (name "GND") (class "Default")
      (node (ref "U1") (pin "P$10") (pinfunction "GND_P$10") (pintype "bidirectional"))
      (node (ref "U10") (pin "P$10") (pinfunction "GND_P$10") (pintype "bidirectional"))
      (node (ref "U11") (pin "P$10") (pinfunction "GND_P$10") (pintype "bidirectional"))
      (node (ref "U12") (pin "P$10") (pinfunction "GND_P$10") (pintype "bidirectional"))
      (node (ref "U13") (pin "P$7") (pinfunction "GND_P$7") (pintype "bidirectional"))
      (node (ref "U2") (pin "P$10") (pinfunction "GND_P$10") (pintype "bidirectional"))
      (node (ref "U3") (pin "P$10") (pinfunction "GND_P$10") (pintype "bidirectional"))
      (node (ref "U4") (pin "P$10") (pinfunction "GND_P$10") (pintype "bidirectional"))
      (node (ref "U6") (pin "P$10") (pinfunction "GND_P$10") (pintype "bidirectional"))
      (node (ref "U7") (pin "P$10") (pinfunction "GND_P$10") (pintype "bidirectional"))
      (node (ref "U8") (pin "P$10") (pinfunction "GND_P$10") (pintype "bidirectional"))
      (node (ref "U9") (pin "P$10") (pinfunction "GND_P$10") (pintype "bidirectional"))
    )
    (net (code "108") (name "Net-(U11-CP)") (class "Default")
      (node (ref "U11") (pin "P$11") (pinfunction "CP_P$11") (pintype "bidirectional"))
      (node (ref "U13") (pin "P$6") (pinfunction "2Y_P$6") (pintype "bidirectional"))
    )
    (net (code "109") (name "Net-(U12-CP)") (class "Default")
      (node (ref "U12") (pin "P$11") (pinfunction "CP_P$11") (pintype "bidirectional"))
      (node (ref "U13") (pin "P$3") (pinfunction "1Y_P$3") (pintype "bidirectional"))
    )
    (net (code "110") (name "Net-(U13-4Y)") (class "Default")
      (node (ref "U13") (pin "P$11") (pinfunction "4Y_P$11") (pintype "bidirectional"))
      (node (ref "U6") (pin "P$11") (pinfunction "CP_P$11") (pintype "bidirectional"))
    )
    (net (code "111") (name "unconnected-(U1-D0-PadP$3)") (class "Default")
      (node (ref "U1") (pin "P$3") (pinfunction "D0_P$3") (pintype "bidirectional"))
    )
    (net (code "112") (name "unconnected-(U1-D1-PadP$4)") (class "Default")
      (node (ref "U1") (pin "P$4") (pinfunction "D1_P$4") (pintype "bidirectional"))
    )
    (net (code "113") (name "unconnected-(U1-D2-PadP$7)") (class "Default")
      (node (ref "U1") (pin "P$7") (pinfunction "D2_P$7") (pintype "bidirectional"))
    )
    (net (code "114") (name "unconnected-(U1-D3-PadP$8)") (class "Default")
      (node (ref "U1") (pin "P$8") (pinfunction "D3_P$8") (pintype "bidirectional"))
    )
    (net (code "115") (name "unconnected-(U1-D4-PadP$13)") (class "Default")
      (node (ref "U1") (pin "P$13") (pinfunction "D4_P$13") (pintype "bidirectional"))
    )
    (net (code "116") (name "unconnected-(U1-D5-PadP$14)") (class "Default")
      (node (ref "U1") (pin "P$14") (pinfunction "D5_P$14") (pintype "bidirectional"))
    )
    (net (code "117") (name "unconnected-(U1-D6-PadP$17)") (class "Default")
      (node (ref "U1") (pin "P$17") (pinfunction "D6_P$17") (pintype "bidirectional"))
    )
    (net (code "118") (name "unconnected-(U1-D7-PadP$18)") (class "Default")
      (node (ref "U1") (pin "P$18") (pinfunction "D7_P$18") (pintype "bidirectional"))
    )
    (net (code "119") (name "unconnected-(U2-D0-PadP$3)") (class "Default")
      (node (ref "U2") (pin "P$3") (pinfunction "D0_P$3") (pintype "bidirectional"))
    )
    (net (code "120") (name "unconnected-(U2-D1-PadP$4)") (class "Default")
      (node (ref "U2") (pin "P$4") (pinfunction "D1_P$4") (pintype "bidirectional"))
    )
    (net (code "121") (name "unconnected-(U2-D2-PadP$7)") (class "Default")
      (node (ref "U2") (pin "P$7") (pinfunction "D2_P$7") (pintype "bidirectional"))
    )
    (net (code "122") (name "unconnected-(U2-D3-PadP$8)") (class "Default")
      (node (ref "U2") (pin "P$8") (pinfunction "D3_P$8") (pintype "bidirectional"))
    )
    (net (code "123") (name "unconnected-(U2-D4-PadP$13)") (class "Default")
      (node (ref "U2") (pin "P$13") (pinfunction "D4_P$13") (pintype "bidirectional"))
    )
    (net (code "124") (name "unconnected-(U2-D5-PadP$14)") (class "Default")
      (node (ref "U2") (pin "P$14") (pinfunction "D5_P$14") (pintype "bidirectional"))
    )
    (net (code "125") (name "unconnected-(U2-D6-PadP$17)") (class "Default")
      (node (ref "U2") (pin "P$17") (pinfunction "D6_P$17") (pintype "bidirectional"))
    )
    (net (code "126") (name "unconnected-(U2-D7-PadP$18)") (class "Default")
      (node (ref "U2") (pin "P$18") (pinfunction "D7_P$18") (pintype "bidirectional"))
    )
    (net (code "127") (name "unconnected-(U3-D0-PadP$3)") (class "Default")
      (node (ref "U3") (pin "P$3") (pinfunction "D0_P$3") (pintype "bidirectional"))
    )
    (net (code "128") (name "unconnected-(U3-D1-PadP$4)") (class "Default")
      (node (ref "U3") (pin "P$4") (pinfunction "D1_P$4") (pintype "bidirectional"))
    )
    (net (code "129") (name "unconnected-(U3-D2-PadP$7)") (class "Default")
      (node (ref "U3") (pin "P$7") (pinfunction "D2_P$7") (pintype "bidirectional"))
    )
    (net (code "130") (name "unconnected-(U3-D3-PadP$8)") (class "Default")
      (node (ref "U3") (pin "P$8") (pinfunction "D3_P$8") (pintype "bidirectional"))
    )
    (net (code "131") (name "unconnected-(U3-D4-PadP$13)") (class "Default")
      (node (ref "U3") (pin "P$13") (pinfunction "D4_P$13") (pintype "bidirectional"))
    )
    (net (code "132") (name "unconnected-(U3-D5-PadP$14)") (class "Default")
      (node (ref "U3") (pin "P$14") (pinfunction "D5_P$14") (pintype "bidirectional"))
    )
    (net (code "133") (name "unconnected-(U3-D6-PadP$17)") (class "Default")
      (node (ref "U3") (pin "P$17") (pinfunction "D6_P$17") (pintype "bidirectional"))
    )
    (net (code "134") (name "unconnected-(U3-D7-PadP$18)") (class "Default")
      (node (ref "U3") (pin "P$18") (pinfunction "D7_P$18") (pintype "bidirectional"))
    )
    (net (code "135") (name "unconnected-(U4-D0-PadP$3)") (class "Default")
      (node (ref "U4") (pin "P$3") (pinfunction "D0_P$3") (pintype "bidirectional"))
    )
    (net (code "136") (name "unconnected-(U4-D1-PadP$4)") (class "Default")
      (node (ref "U4") (pin "P$4") (pinfunction "D1_P$4") (pintype "bidirectional"))
    )
    (net (code "137") (name "unconnected-(U4-D2-PadP$7)") (class "Default")
      (node (ref "U4") (pin "P$7") (pinfunction "D2_P$7") (pintype "bidirectional"))
    )
    (net (code "138") (name "unconnected-(U4-D3-PadP$8)") (class "Default")
      (node (ref "U4") (pin "P$8") (pinfunction "D3_P$8") (pintype "bidirectional"))
    )
    (net (code "139") (name "unconnected-(U4-D4-PadP$13)") (class "Default")
      (node (ref "U4") (pin "P$13") (pinfunction "D4_P$13") (pintype "bidirectional"))
    )
    (net (code "140") (name "unconnected-(U4-D5-PadP$14)") (class "Default")
      (node (ref "U4") (pin "P$14") (pinfunction "D5_P$14") (pintype "bidirectional"))
    )
    (net (code "141") (name "unconnected-(U4-D6-PadP$17)") (class "Default")
      (node (ref "U4") (pin "P$17") (pinfunction "D6_P$17") (pintype "bidirectional"))
    )
    (net (code "142") (name "unconnected-(U4-D7-PadP$18)") (class "Default")
      (node (ref "U4") (pin "P$18") (pinfunction "D7_P$18") (pintype "bidirectional"))
    )
    (net (code "143") (name "unconnected-(U5-CE2-Pad40)") (class "Default")
      (node (ref "U5") (pin "40") (pinfunction "CE2_40") (pintype "bidirectional"))
    )
    (net (code "144") (name "unconnected-(U5-GND_12-Pad12)") (class "Default")
      (node (ref "U5") (pin "12") (pinfunction "GND_12_12") (pintype "bidirectional"))
    )
    (net (code "145") (name "unconnected-(U5-GND_34-Pad34)") (class "Default")
      (node (ref "U5") (pin "34") (pinfunction "GND_34_34") (pintype "bidirectional"))
    )
    (net (code "146") (name "unconnected-(U5-VCC_11-Pad11)") (class "Default")
      (node (ref "U5") (pin "11") (pinfunction "VCC_11_11") (pintype "bidirectional"))
    )
    (net (code "147") (name "unconnected-(U5-VCC_33-Pad33)") (class "Default")
      (node (ref "U5") (pin "33") (pinfunction "VCC_33_33") (pintype "bidirectional"))
    )
    (net (code "148") (name "unconnected-(U5-~{CE}-Pad6)") (class "Default")
      (node (ref "U5") (pin "6") (pinfunction "~{CE}_6") (pintype "bidirectional"))
    )
    (net (code "149") (name "unconnected-(U5-~{OE}-Pad41)") (class "Default")
      (node (ref "U5") (pin "41") (pinfunction "~{OE}_41") (pintype "bidirectional"))
    )
    (net (code "150") (name "unconnected-(U5-~{WE}-Pad17)") (class "Default")
      (node (ref "U5") (pin "17") (pinfunction "~{WE}_17") (pintype "bidirectional"))
    )
    (net (code "151") (name "unconnected-(U7-A5-PadP$7)") (class "Default")
      (node (ref "U7") (pin "P$7") (pinfunction "A5_P$7") (pintype "bidirectional"))
    )
    (net (code "152") (name "unconnected-(U7-A6-PadP$8)") (class "Default")
      (node (ref "U7") (pin "P$8") (pinfunction "A6_P$8") (pintype "bidirectional"))
    )
    (net (code "153") (name "unconnected-(U7-A7-PadP$9)") (class "Default")
      (node (ref "U7") (pin "P$9") (pinfunction "A7_P$9") (pintype "bidirectional"))
    )
    (net (code "154") (name "unconnected-(U7-Y5-PadP$13)") (class "Default")
      (node (ref "U7") (pin "P$13") (pinfunction "Y5_P$13") (pintype "bidirectional"))
    )
    (net (code "155") (name "unconnected-(U7-Y6-PadP$12)") (class "Default")
      (node (ref "U7") (pin "P$12") (pinfunction "Y6_P$12") (pintype "bidirectional"))
    )
    (net (code "156") (name "unconnected-(U7-Y7-PadP$11)") (class "Default")
      (node (ref "U7") (pin "P$11") (pinfunction "Y7_P$11") (pintype "bidirectional"))
    )
  )
)
